# e-ink_sch.net
KiCad netlist of a schematic drawn in Altium Designer
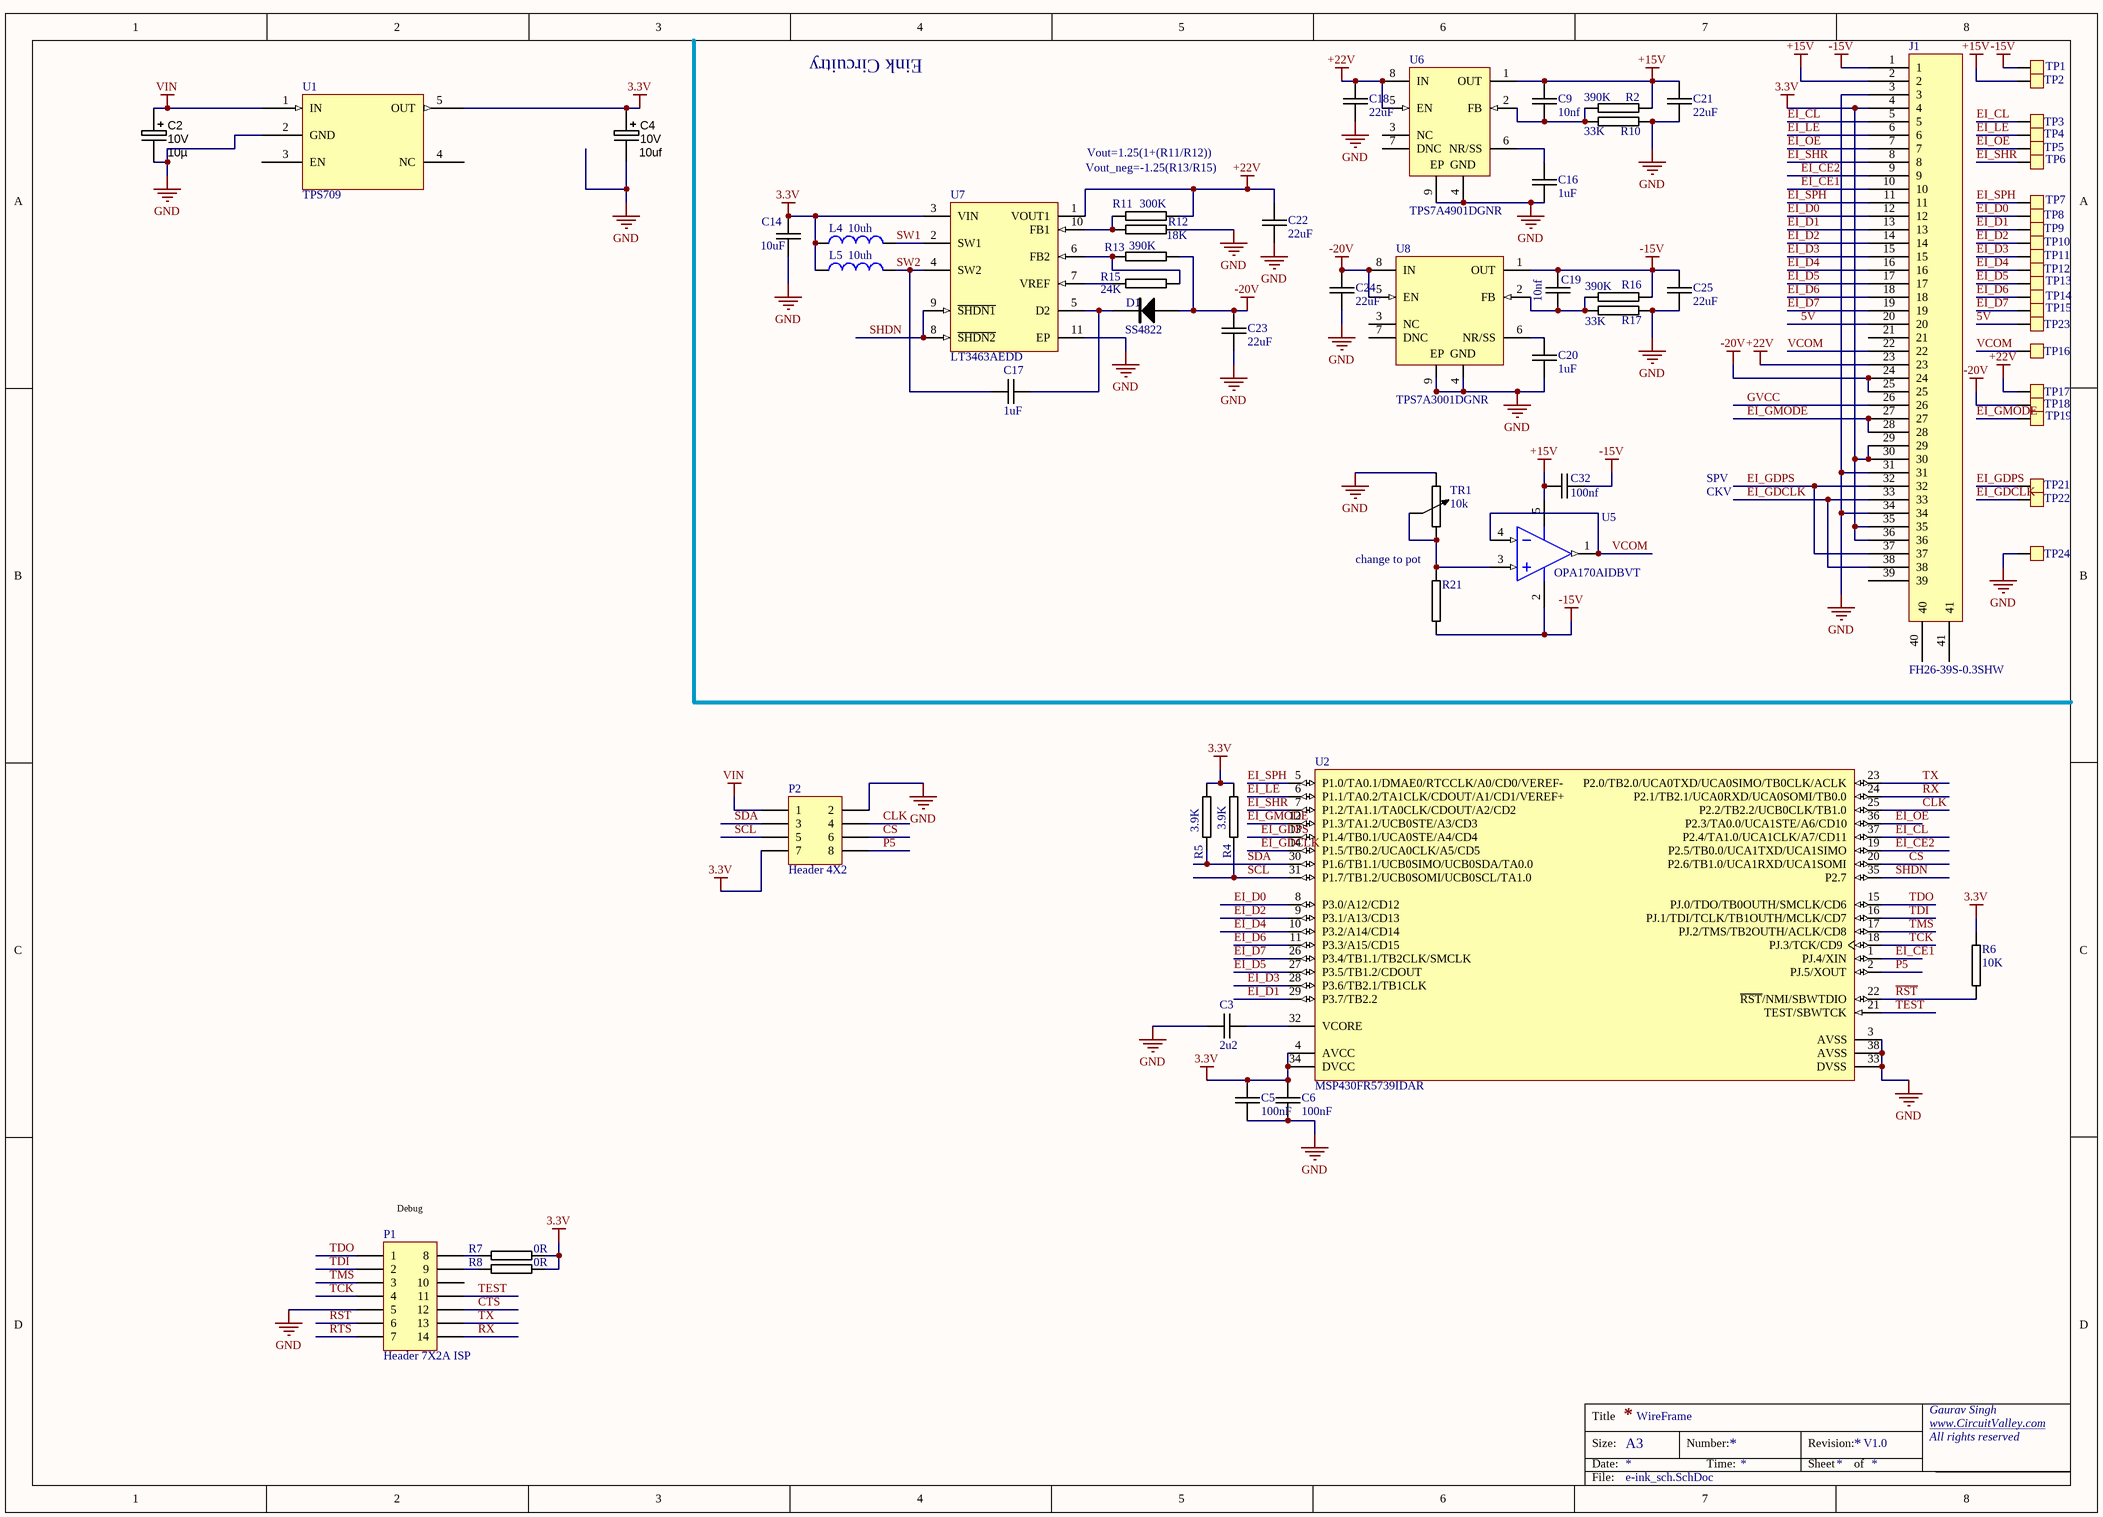
[diagram p0: e-ink_sch.SchDoc]

(export (version "E")
  (design (tool "Eeschema 10.0.6"))
  (components
    (comp (ref "C2")
      (value "10µ")
      (footprint "CAPMP3528X210N")
      (description "Capacitor SMD Tantalum 47uF 20% 6.3V 1210")
      (fields (field (name "TOLERANCE") "±20%") (field (name "RATINGS") "10V"))
      (libsource (lib "PBL - Capacitors") (part "CAPT_47u_1210_6V3"))
    )
    (comp (ref "C3")
      (value "2u2")
      (footprint "0805C-GENERIC")
      (description "CAPACITOR 0805 CERAMIC")
      (fields
        (field (name "MANUFACTURER PART NUMBER") "ECJ-1VB0J225K")
        (field (name "MANUFACTURER") "Panasonic - ECG")
      )
      (libsource (lib "Generic") (part "0805C-2U2-6V3-X5R-PAN"))
    )
    (comp (ref "C4")
      (value "10uf")
      (footprint "CAPMP3528X210N")
      (description "Capacitor SMD Tantalum 47uF 20% 6.3V 1210")
      (fields (field (name "TOLERANCE") "±20%") (field (name "RATINGS") "10V"))
      (libsource (lib "PBL - Capacitors") (part "CAPT_47u_1210_6V3"))
    )
    (comp (ref "C5")
      (value "100nF")
      (footprint "0603C-GENERIC")
      (description "CAPACITOR 0603 CERAMIC")
      (fields
        (field (name "MANUFACTURER PART NUMBER") "C1608X7R1E104K")
        (field (name "MANUFACTURER") "TDK Corporation")
      )
      (libsource (lib "Generic") (part "0603C-100NF-25V-X7R-TDK"))
    )
    (comp (ref "C6")
      (value "100nF")
      (footprint "0603C-GENERIC")
      (description "CAPACITOR 0603 CERAMIC")
      (fields
        (field (name "MANUFACTURER PART NUMBER") "C1608X7R1E104K")
        (field (name "MANUFACTURER") "TDK Corporation")
      )
      (libsource (lib "Generic") (part "0603C-100NF-25V-X7R-TDK"))
    )
    (comp (ref "C9")
      (value "10nf")
      (footprint "0603C-GENERIC")
      (description "CAPACITOR 0603 CERAMIC")
      (fields
        (field (name "MANUFACTURER") "Murata Electronics North America")
        (field (name "MANUFACTURER PART NUMBER") "GRM188R60J106ME47D")
      )
      (libsource (lib "Generic") (part "0603C-10UF-6V3-X5R-MUR"))
    )
    (comp (ref "C14")
      (value "10uF")
      (footprint "0603C-GENERIC")
      (description "CAPACITOR 0603 CERAMIC")
      (fields
        (field (name "MANUFACTURER") "Murata Electronics North America")
        (field (name "MANUFACTURER PART NUMBER") "GRM188R60J106ME47D")
      )
      (libsource (lib "Generic") (part "0603C-10UF-6V3-X5R-MUR"))
    )
    (comp (ref "C16")
      (value "1uF")
      (footprint "0603C-GENERIC")
      (description "CAPACITOR 0603 CERAMIC")
      (fields
        (field (name "MANUFACTURER") "Murata Electronics North America")
        (field (name "MANUFACTURER PART NUMBER") "GRM188R60J106ME47D")
      )
      (libsource (lib "Generic") (part "0603C-10UF-6V3-X5R-MUR"))
    )
    (comp (ref "C17")
      (value "1uF")
      (footprint "0603C-GENERIC")
      (description "CAPACITOR 0603 CERAMIC")
      (fields
        (field (name "MANUFACTURER") "Murata Electronics North America")
        (field (name "MANUFACTURER PART NUMBER") "GRM188R60J106ME47D")
      )
      (libsource (lib "Generic") (part "0603C-10UF-6V3-X5R-MUR"))
    )
    (comp (ref "C18")
      (value "22uF")
      (footprint "0603C-GENERIC")
      (description "CAPACITOR 0603 CERAMIC")
      (fields
        (field (name "MANUFACTURER") "Murata Electronics North America")
        (field (name "MANUFACTURER PART NUMBER") "GRM188R60J106ME47D")
      )
      (libsource (lib "Generic") (part "0603C-10UF-6V3-X5R-MUR"))
    )
    (comp (ref "C19")
      (value "10nf")
      (footprint "0603C-GENERIC")
      (description "CAPACITOR 0603 CERAMIC")
      (fields
        (field (name "MANUFACTURER") "Murata Electronics North America")
        (field (name "MANUFACTURER PART NUMBER") "GRM188R60J106ME47D")
      )
      (libsource (lib "Generic") (part "0603C-10UF-6V3-X5R-MUR"))
    )
    (comp (ref "C20")
      (value "1uF")
      (footprint "0603C-GENERIC")
      (description "CAPACITOR 0603 CERAMIC")
      (fields
        (field (name "MANUFACTURER") "Murata Electronics North America")
        (field (name "MANUFACTURER PART NUMBER") "GRM188R60J106ME47D")
      )
      (libsource (lib "Generic") (part "0603C-10UF-6V3-X5R-MUR"))
    )
    (comp (ref "C21")
      (value "22uF")
      (footprint "0603C-GENERIC")
      (description "CAPACITOR 0603 CERAMIC")
      (fields
        (field (name "MANUFACTURER") "Murata Electronics North America")
        (field (name "MANUFACTURER PART NUMBER") "GRM188R60J106ME47D")
      )
      (libsource (lib "Generic") (part "0603C-10UF-6V3-X5R-MUR"))
    )
    (comp (ref "C22")
      (value "22uF")
      (footprint "0603C-GENERIC")
      (description "CAPACITOR 0603 CERAMIC")
      (fields
        (field (name "MANUFACTURER") "Murata Electronics North America")
        (field (name "MANUFACTURER PART NUMBER") "GRM188R60J106ME47D")
      )
      (libsource (lib "Generic") (part "0603C-10UF-6V3-X5R-MUR"))
    )
    (comp (ref "C23")
      (value "22uF")
      (footprint "0603C-GENERIC")
      (description "CAPACITOR 0603 CERAMIC")
      (fields
        (field (name "MANUFACTURER") "Murata Electronics North America")
        (field (name "MANUFACTURER PART NUMBER") "GRM188R60J106ME47D")
      )
      (libsource (lib "Generic") (part "0603C-10UF-6V3-X5R-MUR"))
    )
    (comp (ref "C24")
      (value "22uF")
      (footprint "0603C-GENERIC")
      (description "CAPACITOR 0603 CERAMIC")
      (fields
        (field (name "MANUFACTURER") "Murata Electronics North America")
        (field (name "MANUFACTURER PART NUMBER") "GRM188R60J106ME47D")
      )
      (libsource (lib "Generic") (part "0603C-10UF-6V3-X5R-MUR"))
    )
    (comp (ref "C25")
      (value "22uF")
      (footprint "0603C-GENERIC")
      (description "CAPACITOR 0603 CERAMIC")
      (fields
        (field (name "MANUFACTURER") "Murata Electronics North America")
        (field (name "MANUFACTURER PART NUMBER") "GRM188R60J106ME47D")
      )
      (libsource (lib "Generic") (part "0603C-10UF-6V3-X5R-MUR"))
    )
    (comp (ref "C32")
      (value "100nf")
      (footprint "0603C-GENERIC")
      (description "CAPACITOR 0603 CERAMIC")
      (fields
        (field (name "MANUFACTURER") "Murata Electronics North America")
        (field (name "MANUFACTURER PART NUMBER") "GRM188R60J106ME47D")
      )
      (libsource (lib "Generic") (part "0603C-10UF-6V3-X5R-MUR"))
    )
    (comp (ref "D1")
      (value "SS4822")
      (footprint "DIODE-SMA")
      (description "DIODE")
      (libsource (lib "Generic") (part "MBRS140"))
    )
    (comp (ref "J1")
      (value "FH26-39S-0.3SHW")
      (footprint "FH26-39S-0.3SHW")
      (libsource (lib "Hiros") (part "FH26-39S-0.3SHW"))
    )
    (comp (ref "L4")
      (value "10uh")
      (footprint "IFSC-1515AH-01")
      (fields (field (name "PARTNUMBER") "IFSC1515AHER100M01"))
      (libsource (lib "Inductor") (part "inductor_smd"))
    )
    (comp (ref "L5")
      (value "10uh")
      (footprint "IFSC-1515AH-01")
      (fields (field (name "PARTNUMBER") "IFSC1515AHER100M01"))
      (libsource (lib "Inductor") (part "inductor_smd"))
    )
    (comp (ref "P1")
      (value "Header 7X2A ISP")
      (footprint "HDR2X7_CEN")
      (description "Header, 7-Pin, Dual row")
      (fields (field (name "PUBLISHER") "Altium Limited"))
      (libsource (lib "Miscellaneous Connectors") (part "Header 7X2A"))
    )
    (comp (ref "P2")
      (value "Header 4X2")
      (footprint "HDR2X4")
      (description "Header, 4-Pin, Dual row")
      (fields (field (name "PUBLISHER") "Altium Limited"))
      (libsource (lib "Miscellaneous Connectors") (part "Header 4X2"))
    )
    (comp (ref "R2")
      (value "390K")
      (footprint "0603R-2K2")
      (description "GENERIC RESISTOR 0603")
      (fields
        (field (name "MANUFACTURER PART NUMBER") "RMC 1/16 2.2K 1% R")
        (field (name "MANUFACTURER") "Stackpole Electronics Inc")
      )
      (libsource (lib "Generic") (part "0603R-2K2"))
    )
    (comp (ref "R4")
      (value "3.9K")
      (footprint "0805R-2K2")
      (description "RESISTOR 0805 1/4 WATT THIN FILM")
      (libsource (lib "Generic") (part "0805R-2K2"))
    )
    (comp (ref "R5")
      (value "3.9K")
      (footprint "0805R-2K2")
      (description "RESISTOR 0805 1/4 WATT THIN FILM")
      (libsource (lib "Generic") (part "0805R-2K2"))
    )
    (comp (ref "R6")
      (value "10K")
      (footprint "0603R-10K")
      (description "GENERIC RESISTOR 0603")
      (fields (field (name "MANUFACTURER") "Stackpole Electronics Inc") (field (name "TOLERANCE") "±1%"))
      (libsource (lib "Generic") (part "0603R-10K"))
    )
    (comp (ref "R7")
      (value "0R")
      (footprint "0805R-2K2")
      (description "RESISTOR 0805 1/4 WATT THIN FILM")
      (libsource (lib "Generic") (part "0805R-2K2"))
    )
    (comp (ref "R8")
      (value "0R")
      (footprint "0805R-2K2")
      (description "RESISTOR 0805 1/4 WATT THIN FILM")
      (libsource (lib "Generic") (part "0805R-2K2"))
    )
    (comp (ref "R10")
      (value "33K")
      (footprint "0603R-2K2")
      (description "GENERIC RESISTOR 0603")
      (fields
        (field (name "MANUFACTURER PART NUMBER") "RMC 1/16 2.2K 1% R")
        (field (name "MANUFACTURER") "Stackpole Electronics Inc")
      )
      (libsource (lib "Generic") (part "0603R-2K2"))
    )
    (comp (ref "R11")
      (value "300K")
      (footprint "0603R-2K2")
      (description "GENERIC RESISTOR 0603")
      (fields
        (field (name "MANUFACTURER PART NUMBER") "RMC 1/16 2.2K 1% R")
        (field (name "MANUFACTURER") "Stackpole Electronics Inc")
      )
      (libsource (lib "Generic") (part "0603R-2K2"))
    )
    (comp (ref "R12")
      (value "18K")
      (footprint "0603R-2K2")
      (description "GENERIC RESISTOR 0603")
      (fields
        (field (name "MANUFACTURER PART NUMBER") "RMC 1/16 2.2K 1% R")
        (field (name "MANUFACTURER") "Stackpole Electronics Inc")
      )
      (libsource (lib "Generic") (part "0603R-2K2"))
    )
    (comp (ref "R13")
      (value "390K")
      (footprint "0603R-2K2")
      (description "GENERIC RESISTOR 0603")
      (fields
        (field (name "MANUFACTURER PART NUMBER") "RMC 1/16 2.2K 1% R")
        (field (name "MANUFACTURER") "Stackpole Electronics Inc")
      )
      (libsource (lib "Generic") (part "0603R-2K2"))
    )
    (comp (ref "R15")
      (value "24K")
      (footprint "0603R-2K2")
      (description "GENERIC RESISTOR 0603")
      (fields
        (field (name "MANUFACTURER PART NUMBER") "RMC 1/16 2.2K 1% R")
        (field (name "MANUFACTURER") "Stackpole Electronics Inc")
      )
      (libsource (lib "Generic") (part "0603R-2K2"))
    )
    (comp (ref "R16")
      (value "390K")
      (footprint "0603R-2K2")
      (description "GENERIC RESISTOR 0603")
      (fields
        (field (name "MANUFACTURER PART NUMBER") "RMC 1/16 2.2K 1% R")
        (field (name "MANUFACTURER") "Stackpole Electronics Inc")
      )
      (libsource (lib "Generic") (part "0603R-2K2"))
    )
    (comp (ref "R17")
      (value "33K")
      (footprint "0603R-2K2")
      (description "GENERIC RESISTOR 0603")
      (fields
        (field (name "MANUFACTURER PART NUMBER") "RMC 1/16 2.2K 1% R")
        (field (name "MANUFACTURER") "Stackpole Electronics Inc")
      )
      (libsource (lib "Generic") (part "0603R-2K2"))
    )
    (comp (ref "R21")
      (value "unknown")
      (footprint "0603R-2K2")
      (description "GENERIC RESISTOR 0603")
      (fields
        (field (name "MANUFACTURER PART NUMBER") "RMC 1/16 2.2K 1% R")
        (field (name "MANUFACTURER") "Stackpole Electronics Inc")
      )
      (libsource (lib "Generic") (part "0603R-2K2"))
    )
    (comp (ref "TP1")
      (value "TEST_POINT")
      (footprint "SMD_TEST_3.5_2.0")
      (libsource (lib "SMD_TEST_PAD") (part "TEST_POINT"))
    )
    (comp (ref "TP2")
      (value "TEST_POINT")
      (footprint "SMD_TEST_3.5_2.0")
      (libsource (lib "SMD_TEST_PAD") (part "TEST_POINT"))
    )
    (comp (ref "TP3")
      (value "TEST_POINT")
      (footprint "SMD_TEST_3.5_2.0")
      (libsource (lib "SMD_TEST_PAD") (part "TEST_POINT"))
    )
    (comp (ref "TP4")
      (value "TEST_POINT")
      (footprint "SMD_TEST_3.5_2.0")
      (libsource (lib "SMD_TEST_PAD") (part "TEST_POINT"))
    )
    (comp (ref "TP5")
      (value "TEST_POINT")
      (footprint "SMD_TEST_3.5_2.0")
      (libsource (lib "SMD_TEST_PAD") (part "TEST_POINT"))
    )
    (comp (ref "TP6")
      (value "TEST_POINT")
      (footprint "SMD_TEST_3.5_2.0")
      (libsource (lib "SMD_TEST_PAD") (part "TEST_POINT"))
    )
    (comp (ref "TP7")
      (value "TEST_POINT")
      (footprint "SMD_TEST_3.5_2.0")
      (libsource (lib "SMD_TEST_PAD") (part "TEST_POINT"))
    )
    (comp (ref "TP8")
      (value "TEST_POINT")
      (footprint "SMD_TEST_3.5_2.0")
      (libsource (lib "SMD_TEST_PAD") (part "TEST_POINT"))
    )
    (comp (ref "TP9")
      (value "TEST_POINT")
      (footprint "SMD_TEST_3.5_2.0")
      (libsource (lib "SMD_TEST_PAD") (part "TEST_POINT"))
    )
    (comp (ref "TP10")
      (value "TEST_POINT")
      (footprint "SMD_TEST_3.5_2.0")
      (libsource (lib "SMD_TEST_PAD") (part "TEST_POINT"))
    )
    (comp (ref "TP11")
      (value "TEST_POINT")
      (footprint "SMD_TEST_3.5_2.0")
      (libsource (lib "SMD_TEST_PAD") (part "TEST_POINT"))
    )
    (comp (ref "TP12")
      (value "TEST_POINT")
      (footprint "SMD_TEST_3.5_2.0")
      (libsource (lib "SMD_TEST_PAD") (part "TEST_POINT"))
    )
    (comp (ref "TP13")
      (value "TEST_POINT")
      (footprint "SMD_TEST_3.5_2.0")
      (libsource (lib "SMD_TEST_PAD") (part "TEST_POINT"))
    )
    (comp (ref "TP14")
      (value "TEST_POINT")
      (footprint "SMD_TEST_3.5_2.0")
      (libsource (lib "SMD_TEST_PAD") (part "TEST_POINT"))
    )
    (comp (ref "TP15")
      (value "TEST_POINT")
      (footprint "SMD_TEST_3.5_2.0")
      (libsource (lib "SMD_TEST_PAD") (part "TEST_POINT"))
    )
    (comp (ref "TP16")
      (value "TEST_POINT")
      (footprint "SMD_TEST_3.5_2.0")
      (libsource (lib "SMD_TEST_PAD") (part "TEST_POINT"))
    )
    (comp (ref "TP17")
      (value "TEST_POINT")
      (footprint "SMD_TEST_3.5_2.0")
      (libsource (lib "SMD_TEST_PAD") (part "TEST_POINT"))
    )
    (comp (ref "TP18")
      (value "TEST_POINT")
      (footprint "SMD_TEST_3.5_2.0")
      (libsource (lib "SMD_TEST_PAD") (part "TEST_POINT"))
    )
    (comp (ref "TP19")
      (value "TEST_POINT")
      (footprint "SMD_TEST_3.5_2.0")
      (libsource (lib "SMD_TEST_PAD") (part "TEST_POINT"))
    )
    (comp (ref "TP21")
      (value "TEST_POINT")
      (footprint "SMD_TEST_3.5_2.0")
      (libsource (lib "SMD_TEST_PAD") (part "TEST_POINT"))
    )
    (comp (ref "TP22")
      (value "TEST_POINT")
      (footprint "SMD_TEST_3.5_2.0")
      (libsource (lib "SMD_TEST_PAD") (part "TEST_POINT"))
    )
    (comp (ref "TP23")
      (value "TEST_POINT")
      (footprint "SMD_TEST_3.5_2.0")
      (libsource (lib "SMD_TEST_PAD") (part "TEST_POINT"))
    )
    (comp (ref "TP24")
      (value "TEST_POINT")
      (footprint "SMD_TEST_3.5_2.0")
      (libsource (lib "SMD_TEST_PAD") (part "TEST_POINT"))
    )
    (comp (ref "TR1")
      (value "10k")
      (footprint "SMDPOT")
      (description "GENERIC SMD TRIMMER")
      (fields (field (name "TOLERANCE") "±10%") (field (name "MANUFACTURER PART NUMBER") "3224X-1-103E"))
      (libsource (lib "Generic") (part "R-TRIM-SMD-10k"))
    )
    (comp (ref "U1") (value "TPS709") (footprint "SOT23-5") (libsource (lib "LDO_reg") (part "TPS709")))
    (comp (ref "U2")
      (value "MSP430FR5739IDAR")
      (footprint "TI-DA38_N")
      (fields (field (name "MANUFACTURER") "Texas Instruments"))
      (libsource (lib "TI Microcontroller MSP430 16-bit Ultra-Low Power") (part "MSP430FR5739IDAR"))
    )
    (comp (ref "U5")
      (value "OPA170AIDBVT")
      (footprint "TI-DBV5_N")
      (fields (field (name "MANUFACTURER") "Texas Instruments"))
      (libsource (lib "TI Amplifiers and Linear Operational Amplifier Precision Amplifier Part One") (part "OPA244NA/250"))
    )
    (comp (ref "U6")
      (value "TPS7A4901DGNR")
      (footprint "TI-DGN8-1760X1425TP_N")
      (fields (field (name "MANUFACTURER") "Texas Instruments"))
      (libsource (lib "TI Power Management Linear Regulator Single Channel LDO (0-350mA)") (part "TPS7A4901DGNR"))
    )
    (comp (ref "U7")
      (value "LT3463AEDD")
      (footprint "LT-DD-10_V")
      (fields (field (name "MANUFACTURER") "Linear Technology"))
      (libsource (lib "Linear Technology Power Management PMIC Multifunction") (part "LT3463AEDD"))
    )
    (comp (ref "U8")
      (value "TPS7A3001DGNR")
      (footprint "TI-DGN8-1760X1425TP_N")
      (fields (field (name "MANUFACTURER") "Texas Instruments"))
      (libsource (lib "TI Power Management Linear Regulator Single Channel LDO (0-350mA)") (part "TPS7A3001DGNR"))
    )
  )
  (nets
    (net (code "1") (name "+15V") (class "Default")
      (node (ref "C21") (pin "2") (pintype "passive"))
      (node (ref "C32") (pin "2") (pintype "passive"))
      (node (ref "C9") (pin "1") (pintype "passive"))
      (node (ref "J1") (pin "2") (pinfunction "2_2") (pintype "passive"))
      (node (ref "R2") (pin "2") (pintype "passive"))
      (node (ref "TP2") (pin "0") (pinfunction "0_0") (pintype "passive"))
      (node (ref "U5") (pin "5") (pinfunction "V+_5") (pintype "power_in"))
      (node (ref "U6") (pin "1") (pinfunction "OUT_1") (pintype "power_in"))
    )
    (net (code "2") (name "+22V") (class "Default")
      (node (ref "C18") (pin "2") (pintype "passive"))
      (node (ref "C22") (pin "2") (pintype "passive"))
      (node (ref "J1") (pin "23") (pinfunction "23_23") (pintype "passive"))
      (node (ref "R11") (pin "2") (pintype "passive"))
      (node (ref "TP17") (pin "0") (pinfunction "0_0") (pintype "passive"))
      (node (ref "U6") (pin "5") (pinfunction "EN_5") (pintype "input"))
      (node (ref "U6") (pin "8") (pinfunction "IN_8") (pintype "power_in"))
      (node (ref "U7") (pin "1") (pinfunction "VOUT1_1") (pintype "power_in"))
    )
    (net (code "3") (name "-15V") (class "Default")
      (node (ref "C19") (pin "1") (pintype "passive"))
      (node (ref "C25") (pin "2") (pintype "passive"))
      (node (ref "C32") (pin "1") (pintype "passive"))
      (node (ref "J1") (pin "1") (pinfunction "1_1") (pintype "passive"))
      (node (ref "R16") (pin "2") (pintype "passive"))
      (node (ref "R21") (pin "1") (pintype "passive"))
      (node (ref "TP1") (pin "0") (pinfunction "0_0") (pintype "passive"))
      (node (ref "U5") (pin "2") (pinfunction "V-_2") (pintype "power_in"))
      (node (ref "U8") (pin "1") (pinfunction "OUT_1") (pintype "power_in"))
    )
    (net (code "4") (name "-20V") (class "Default")
      (node (ref "C23") (pin "2") (pintype "passive"))
      (node (ref "C24") (pin "2") (pintype "passive"))
      (node (ref "D1") (pin "A") (pinfunction "A_A") (pintype "passive"))
      (node (ref "J1") (pin "24") (pinfunction "24_24") (pintype "passive"))
      (node (ref "J1") (pin "25") (pinfunction "25_25") (pintype "passive"))
      (node (ref "R13") (pin "2") (pintype "passive"))
      (node (ref "TP18") (pin "0") (pinfunction "0_0") (pintype "passive"))
      (node (ref "U8") (pin "5") (pinfunction "EN_5") (pintype "input"))
      (node (ref "U8") (pin "8") (pinfunction "IN_8") (pintype "power_in"))
    )
    (net (code "5") (name "/5V") (class "Default")
      (node (ref "J1") (pin "20") (pinfunction "20_20") (pintype "passive"))
      (node (ref "TP23") (pin "0") (pinfunction "0_0") (pintype "passive"))
    )
    (net (code "6") (name "/CLK") (class "Default")
      (node (ref "P2") (pin "4") (pinfunction "4_4") (pintype "passive"))
      (node (ref "U2") (pin "25") (pinfunction "P2.2/TB2.2/UCB0CLK/TB1.0_25") (pintype "bidirectional"))
    )
    (net (code "7") (name "/CS") (class "Default")
      (node (ref "P2") (pin "6") (pinfunction "6_6") (pintype "passive"))
      (node (ref "U2") (pin "20") (pinfunction "P2.6/TB1.0/UCA1RXD/UCA1SOMI_20") (pintype "bidirectional"))
    )
    (net (code "8") (name "/CTS") (class "Default")
      (node (ref "P1") (pin "12") (pinfunction "12_12") (pintype "passive"))
    )
    (net (code "9") (name "/EI_CE1") (class "Default")
      (node (ref "J1") (pin "10") (pinfunction "10_10") (pintype "passive"))
      (node (ref "U2") (pin "1") (pinfunction "PJ.4/XIN_1") (pintype "bidirectional"))
    )
    (net (code "10") (name "/EI_CE2") (class "Default")
      (node (ref "J1") (pin "9") (pinfunction "9_9") (pintype "passive"))
      (node (ref "U2") (pin "19") (pinfunction "P2.5/TB0.0/UCA1TXD/UCA1SIMO_19") (pintype "bidirectional"))
    )
    (net (code "11") (name "/EI_CL") (class "Default")
      (node (ref "J1") (pin "5") (pinfunction "5_5") (pintype "passive"))
      (node (ref "TP3") (pin "0") (pinfunction "0_0") (pintype "passive"))
      (node (ref "U2") (pin "37") (pinfunction "P2.4/TA1.0/UCA1CLK/A7/CD11_37") (pintype "bidirectional"))
    )
    (net (code "12") (name "/EI_D0") (class "Default")
      (node (ref "J1") (pin "12") (pinfunction "12_12") (pintype "passive"))
      (node (ref "TP8") (pin "0") (pinfunction "0_0") (pintype "passive"))
      (node (ref "U2") (pin "8") (pinfunction "P3.0/A12/CD12_8") (pintype "bidirectional"))
    )
    (net (code "13") (name "/EI_D1") (class "Default")
      (node (ref "J1") (pin "13") (pinfunction "13_13") (pintype "passive"))
      (node (ref "TP9") (pin "0") (pinfunction "0_0") (pintype "passive"))
      (node (ref "U2") (pin "29") (pinfunction "P3.7/TB2.2_29") (pintype "bidirectional"))
    )
    (net (code "14") (name "/EI_D2") (class "Default")
      (node (ref "J1") (pin "14") (pinfunction "14_14") (pintype "passive"))
      (node (ref "TP10") (pin "0") (pinfunction "0_0") (pintype "passive"))
      (node (ref "U2") (pin "9") (pinfunction "P3.1/A13/CD13_9") (pintype "bidirectional"))
    )
    (net (code "15") (name "/EI_D3") (class "Default")
      (node (ref "J1") (pin "15") (pinfunction "15_15") (pintype "passive"))
      (node (ref "TP11") (pin "0") (pinfunction "0_0") (pintype "passive"))
      (node (ref "U2") (pin "28") (pinfunction "P3.6/TB2.1/TB1CLK_28") (pintype "bidirectional"))
    )
    (net (code "16") (name "/EI_D4") (class "Default")
      (node (ref "J1") (pin "16") (pinfunction "16_16") (pintype "passive"))
      (node (ref "TP12") (pin "0") (pinfunction "0_0") (pintype "passive"))
      (node (ref "U2") (pin "10") (pinfunction "P3.2/A14/CD14_10") (pintype "bidirectional"))
    )
    (net (code "17") (name "/EI_D5") (class "Default")
      (node (ref "J1") (pin "17") (pinfunction "17_17") (pintype "passive"))
      (node (ref "TP13") (pin "0") (pinfunction "0_0") (pintype "passive"))
      (node (ref "U2") (pin "27") (pinfunction "P3.5/TB1.2/CDOUT_27") (pintype "bidirectional"))
    )
    (net (code "18") (name "/EI_D6") (class "Default")
      (node (ref "J1") (pin "18") (pinfunction "18_18") (pintype "passive"))
      (node (ref "TP14") (pin "0") (pinfunction "0_0") (pintype "passive"))
      (node (ref "U2") (pin "11") (pinfunction "P3.3/A15/CD15_11") (pintype "bidirectional"))
    )
    (net (code "19") (name "/EI_D7") (class "Default")
      (node (ref "J1") (pin "19") (pinfunction "19_19") (pintype "passive"))
      (node (ref "TP15") (pin "0") (pinfunction "0_0") (pintype "passive"))
      (node (ref "U2") (pin "26") (pinfunction "P3.4/TB1.1/TB2CLK/SMCLK_26") (pintype "bidirectional"))
    )
    (net (code "20") (name "/EI_GDCLK") (class "Default")
      (node (ref "J1") (pin "33") (pinfunction "33_33") (pintype "passive"))
      (node (ref "J1") (pin "38") (pinfunction "38_38") (pintype "passive"))
      (node (ref "TP22") (pin "0") (pinfunction "0_0") (pintype "passive"))
      (node (ref "U2") (pin "14") (pinfunction "P1.5/TB0.2/UCA0CLK/A5/CD5_14") (pintype "bidirectional"))
    )
    (net (code "21") (name "/EI_GDPS") (class "Default")
      (node (ref "J1") (pin "32") (pinfunction "32_32") (pintype "passive"))
      (node (ref "J1") (pin "37") (pinfunction "37_37") (pintype "passive"))
      (node (ref "TP21") (pin "0") (pinfunction "0_0") (pintype "passive"))
      (node (ref "U2") (pin "13") (pinfunction "P1.4/TB0.1/UCA0STE/A4/CD4_13") (pintype "bidirectional"))
    )
    (net (code "22") (name "/EI_GMODE") (class "Default")
      (node (ref "J1") (pin "27") (pinfunction "27_27") (pintype "passive"))
      (node (ref "J1") (pin "28") (pinfunction "28_28") (pintype "passive"))
      (node (ref "TP19") (pin "0") (pinfunction "0_0") (pintype "passive"))
      (node (ref "U2") (pin "12") (pinfunction "P1.3/TA1.2/UCB0STE/A3/CD3_12") (pintype "bidirectional"))
    )
    (net (code "23") (name "/EI_LE") (class "Default")
      (node (ref "J1") (pin "6") (pinfunction "6_6") (pintype "passive"))
      (node (ref "TP4") (pin "0") (pinfunction "0_0") (pintype "passive"))
      (node (ref "U2") (pin "6") (pinfunction "P1.1/TA0.2/TA1CLK/CDOUT/A1/CD1/VEREF+_6") (pintype "bidirectional"))
    )
    (net (code "24") (name "/EI_OE") (class "Default")
      (node (ref "J1") (pin "7") (pinfunction "7_7") (pintype "passive"))
      (node (ref "TP5") (pin "0") (pinfunction "0_0") (pintype "passive"))
      (node (ref "U2") (pin "36") (pinfunction "P2.3/TA0.0/UCA1STE/A6/CD10_36") (pintype "bidirectional"))
    )
    (net (code "25") (name "/EI_SHR") (class "Default")
      (node (ref "J1") (pin "8") (pinfunction "8_8") (pintype "passive"))
      (node (ref "TP6") (pin "0") (pinfunction "0_0") (pintype "passive"))
      (node (ref "U2") (pin "7") (pinfunction "P1.2/TA1.1/TA0CLK/CDOUT/A2/CD2_7") (pintype "bidirectional"))
    )
    (net (code "26") (name "/EI_SPH") (class "Default")
      (node (ref "J1") (pin "11") (pinfunction "11_11") (pintype "passive"))
      (node (ref "TP7") (pin "0") (pinfunction "0_0") (pintype "passive"))
      (node (ref "U2") (pin "5") (pinfunction "P1.0/TA0.1/DMAE0/RTCCLK/A0/CD0/VEREF-_5") (pintype "bidirectional"))
    )
    (net (code "27") (name "/GVCC") (class "Default")
      (node (ref "J1") (pin "26") (pinfunction "26_26") (pintype "passive"))
    )
    (net (code "28") (name "/P5") (class "Default")
      (node (ref "P2") (pin "8") (pinfunction "8_8") (pintype "passive"))
      (node (ref "U2") (pin "2") (pinfunction "PJ.5/XOUT_2") (pintype "bidirectional"))
    )
    (net (code "29") (name "/RTS") (class "Default")
      (node (ref "P1") (pin "7") (pinfunction "7_7") (pintype "passive"))
    )
    (net (code "30") (name "/RX") (class "Default")
      (node (ref "P1") (pin "14") (pinfunction "14_14") (pintype "passive"))
      (node (ref "U2") (pin "24") (pinfunction "P2.1/TB2.1/UCA0RXD/UCA0SOMI/TB0.0_24") (pintype "bidirectional"))
    )
    (net (code "31") (name "/SCL") (class "Default")
      (node (ref "P2") (pin "5") (pinfunction "5_5") (pintype "passive"))
      (node (ref "R4") (pin "1") (pintype "passive"))
      (node (ref "U2") (pin "31") (pinfunction "P1.7/TB1.2/UCB0SOMI/UCB0SCL/TA1.0_31") (pintype "bidirectional"))
    )
    (net (code "32") (name "/SDA") (class "Default")
      (node (ref "P2") (pin "3") (pinfunction "3_3") (pintype "passive"))
      (node (ref "R5") (pin "1") (pintype "passive"))
      (node (ref "U2") (pin "30") (pinfunction "P1.6/TB1.1/UCB0SIMO/UCB0SDA/TA0.0_30") (pintype "bidirectional"))
    )
    (net (code "33") (name "/SHDN") (class "Default")
      (node (ref "U2") (pin "35") (pinfunction "P2.7_35") (pintype "bidirectional"))
      (node (ref "U7") (pin "8") (pinfunction "~{SHDN2}_8") (pintype "input"))
      (node (ref "U7") (pin "9") (pinfunction "~{SHDN1}_9") (pintype "input"))
    )
    (net (code "34") (name "/SW1") (class "Default")
      (node (ref "L4") (pin "2") (pinfunction "2_2") (pintype "passive"))
      (node (ref "U7") (pin "2") (pinfunction "SW1_2") (pintype "passive"))
    )
    (net (code "35") (name "/SW2") (class "Default")
      (node (ref "C17") (pin "2") (pintype "passive"))
      (node (ref "L5") (pin "2") (pinfunction "2_2") (pintype "passive"))
      (node (ref "U7") (pin "4") (pinfunction "SW2_4") (pintype "passive"))
    )
    (net (code "36") (name "/TCK") (class "Default")
      (node (ref "P1") (pin "4") (pinfunction "4_4") (pintype "passive"))
      (node (ref "U2") (pin "18") (pinfunction "PJ.3/TCK/CD9_18") (pintype "bidirectional"))
    )
    (net (code "37") (name "/TDI") (class "Default")
      (node (ref "P1") (pin "2") (pinfunction "2_2") (pintype "passive"))
      (node (ref "U2") (pin "16") (pinfunction "PJ.1/TDI/TCLK/TB1OUTH/MCLK/CD7_16") (pintype "bidirectional"))
    )
    (net (code "38") (name "/TDO") (class "Default")
      (node (ref "P1") (pin "1") (pinfunction "1_1") (pintype "passive"))
      (node (ref "U2") (pin "15") (pinfunction "PJ.0/TDO/TB0OUTH/SMCLK/CD6_15") (pintype "bidirectional"))
    )
    (net (code "39") (name "/TEST") (class "Default")
      (node (ref "P1") (pin "11") (pinfunction "11_11") (pintype "passive"))
      (node (ref "U2") (pin "21") (pinfunction "TEST/SBWTCK_21") (pintype "input"))
    )
    (net (code "40") (name "/TMS") (class "Default")
      (node (ref "P1") (pin "3") (pinfunction "3_3") (pintype "passive"))
      (node (ref "U2") (pin "17") (pinfunction "PJ.2/TMS/TB2OUTH/ACLK/CD8_17") (pintype "bidirectional"))
    )
    (net (code "41") (name "/TX") (class "Default")
      (node (ref "P1") (pin "13") (pinfunction "13_13") (pintype "passive"))
      (node (ref "U2") (pin "23") (pinfunction "P2.0/TB2.0/UCA0TXD/UCA0SIMO/TB0CLK/ACLK_23") (pintype "bidirectional"))
    )
    (net (code "42") (name "/VCOM") (class "Default")
      (node (ref "J1") (pin "22") (pinfunction "22_22") (pintype "passive"))
      (node (ref "TP16") (pin "0") (pinfunction "0_0") (pintype "passive"))
      (node (ref "U5") (pin "1") (pinfunction "OUT_1") (pintype "output"))
      (node (ref "U5") (pin "4") (pinfunction "IN-_4") (pintype "input"))
    )
    (net (code "43") (name "/~{RST}") (class "Default")
      (node (ref "P1") (pin "6") (pinfunction "6_6") (pintype "passive"))
      (node (ref "R6") (pin "2") (pintype "passive"))
      (node (ref "U2") (pin "22") (pinfunction "~{RST}/NMI/SBWTDIO_22") (pintype "bidirectional"))
    )
    (net (code "44") (name "3.3V") (class "Default")
      (node (ref "C14") (pin "2") (pintype "passive"))
      (node (ref "C4") (pin "1") (pintype "passive"))
      (node (ref "C5") (pin "1") (pintype "passive"))
      (node (ref "C6") (pin "1") (pintype "passive"))
      (node (ref "J1") (pin "29") (pinfunction "29_29") (pintype "passive"))
      (node (ref "J1") (pin "30") (pinfunction "30_30") (pintype "passive"))
      (node (ref "J1") (pin "35") (pinfunction "35_35") (pintype "passive"))
      (node (ref "J1") (pin "36") (pinfunction "36_36") (pintype "passive"))
      (node (ref "J1") (pin "4") (pinfunction "4_4") (pintype "passive"))
      (node (ref "L4") (pin "1") (pinfunction "1_1") (pintype "passive"))
      (node (ref "L5") (pin "1") (pinfunction "1_1") (pintype "passive"))
      (node (ref "P2") (pin "7") (pinfunction "7_7") (pintype "passive"))
      (node (ref "R4") (pin "2") (pintype "passive"))
      (node (ref "R5") (pin "2") (pintype "passive"))
      (node (ref "R6") (pin "1") (pintype "passive"))
      (node (ref "R7") (pin "1") (pintype "passive"))
      (node (ref "R8") (pin "1") (pintype "passive"))
      (node (ref "U1") (pin "5") (pinfunction "OUT_5") (pintype "output"))
      (node (ref "U2") (pin "34") (pinfunction "DVCC_34") (pintype "power_in"))
      (node (ref "U2") (pin "4") (pinfunction "AVCC_4") (pintype "power_in"))
      (node (ref "U7") (pin "3") (pinfunction "VIN_3") (pintype "power_in"))
    )
    (net (code "45") (name "GND") (class "Default")
      (node (ref "C14") (pin "1") (pintype "passive"))
      (node (ref "C16") (pin "1") (pintype "passive"))
      (node (ref "C18") (pin "1") (pintype "passive"))
      (node (ref "C2") (pin "2") (pintype "passive"))
      (node (ref "C20") (pin "2") (pintype "passive"))
      (node (ref "C21") (pin "1") (pintype "passive"))
      (node (ref "C22") (pin "1") (pintype "passive"))
      (node (ref "C23") (pin "1") (pintype "passive"))
      (node (ref "C24") (pin "1") (pintype "passive"))
      (node (ref "C25") (pin "1") (pintype "passive"))
      (node (ref "C3") (pin "1") (pintype "passive"))
      (node (ref "C4") (pin "2") (pintype "passive"))
      (node (ref "C5") (pin "2") (pintype "passive"))
      (node (ref "C6") (pin "2") (pintype "passive"))
      (node (ref "J1") (pin "3") (pinfunction "3_3") (pintype "passive"))
      (node (ref "J1") (pin "31") (pinfunction "31_31") (pintype "passive"))
      (node (ref "J1") (pin "34") (pinfunction "34_34") (pintype "passive"))
      (node (ref "P1") (pin "5") (pinfunction "5_5") (pintype "passive"))
      (node (ref "P2") (pin "2") (pinfunction "2_2") (pintype "passive"))
      (node (ref "R10") (pin "2") (pintype "passive"))
      (node (ref "R12") (pin "1") (pintype "passive"))
      (node (ref "R17") (pin "2") (pintype "passive"))
      (node (ref "TP24") (pin "0") (pinfunction "0_0") (pintype "passive"))
      (node (ref "TR1") (pin "2") (pinfunction "2_2") (pintype "passive"))
      (node (ref "U1") (pin "2") (pinfunction "GND_2") (pintype "power_in"))
      (node (ref "U2") (pin "3") (pinfunction "AVSS_3") (pintype "power_in"))
      (node (ref "U2") (pin "33") (pinfunction "DVSS_33") (pintype "power_in"))
      (node (ref "U2") (pin "38") (pinfunction "AVSS_38") (pintype "power_in"))
      (node (ref "U6") (pin "4") (pinfunction "GND_4") (pintype "power_in"))
      (node (ref "U6") (pin "9") (pinfunction "EP_9") (pintype "power_in"))
      (node (ref "U7") (pin "11") (pinfunction "EP_11") (pintype "power_in"))
      (node (ref "U8") (pin "4") (pinfunction "GND_4") (pintype "power_in"))
      (node (ref "U8") (pin "9") (pinfunction "EP_9") (pintype "passive"))
    )
    (net (code "46") (name "Net-(P1-Pad8)") (class "Default")
      (node (ref "P1") (pin "8") (pinfunction "8_8") (pintype "passive"))
      (node (ref "R7") (pin "2") (pintype "passive"))
    )
    (net (code "47") (name "Net-(P1-Pad9)") (class "Default")
      (node (ref "P1") (pin "9") (pinfunction "9_9") (pintype "passive"))
      (node (ref "R8") (pin "2") (pintype "passive"))
    )
    (net (code "48") (name "Net-(U2-VCORE)") (class "Default")
      (node (ref "C3") (pin "2") (pintype "passive"))
      (node (ref "U2") (pin "32") (pinfunction "VCORE_32") (pintype "passive"))
    )
    (net (code "49") (name "Net-(U5-IN+)") (class "Default")
      (node (ref "R21") (pin "2") (pintype "passive"))
      (node (ref "TR1") (pin "1") (pinfunction "1_1") (pintype "passive"))
      (node (ref "TR1") (pin "W") (pinfunction "W_W") (pintype "passive"))
      (node (ref "U5") (pin "3") (pinfunction "IN+_3") (pintype "input"))
    )
    (net (code "50") (name "Net-(U6-FB)") (class "Default")
      (node (ref "C9") (pin "2") (pintype "passive"))
      (node (ref "R10") (pin "1") (pintype "passive"))
      (node (ref "R2") (pin "1") (pintype "passive"))
      (node (ref "U6") (pin "2") (pinfunction "FB_2") (pintype "input"))
    )
    (net (code "51") (name "Net-(U6-NR{slash}SS)") (class "Default")
      (node (ref "C16") (pin "2") (pintype "passive"))
      (node (ref "U6") (pin "6") (pinfunction "NR/SS_6") (pintype "passive"))
    )
    (net (code "52") (name "Net-(U7-D2)") (class "Default")
      (node (ref "C17") (pin "1") (pintype "passive"))
      (node (ref "D1") (pin "K") (pinfunction "K_K") (pintype "passive"))
      (node (ref "U7") (pin "5") (pinfunction "D2_5") (pintype "passive"))
    )
    (net (code "53") (name "Net-(U7-FB1)") (class "Default")
      (node (ref "R11") (pin "1") (pintype "passive"))
      (node (ref "R12") (pin "2") (pintype "passive"))
      (node (ref "U7") (pin "10") (pinfunction "FB1_10") (pintype "input"))
    )
    (net (code "54") (name "Net-(U7-FB2)") (class "Default")
      (node (ref "R13") (pin "1") (pintype "passive"))
      (node (ref "R15") (pin "2") (pintype "passive"))
      (node (ref "U7") (pin "6") (pinfunction "FB2_6") (pintype "input"))
    )
    (net (code "55") (name "Net-(U7-VREF)") (class "Default")
      (node (ref "R15") (pin "1") (pintype "passive"))
      (node (ref "U7") (pin "7") (pinfunction "VREF_7") (pintype "input"))
    )
    (net (code "56") (name "Net-(U8-FB)") (class "Default")
      (node (ref "C19") (pin "2") (pintype "passive"))
      (node (ref "R16") (pin "1") (pintype "passive"))
      (node (ref "R17") (pin "1") (pintype "passive"))
      (node (ref "U8") (pin "2") (pinfunction "FB_2") (pintype "input"))
    )
    (net (code "57") (name "Net-(U8-NR{slash}SS)") (class "Default")
      (node (ref "C20") (pin "1") (pintype "passive"))
      (node (ref "U8") (pin "6") (pinfunction "NR/SS_6") (pintype "passive"))
    )
    (net (code "58") (name "VIN") (class "Default")
      (node (ref "C2") (pin "1") (pintype "passive"))
      (node (ref "P2") (pin "1") (pinfunction "1_1") (pintype "passive"))
      (node (ref "U1") (pin "1") (pinfunction "IN_1") (pintype "input"))
    )
    (net (code "59") (name "unconnected-(J1-Pad21)") (class "Default")
      (node (ref "J1") (pin "21") (pinfunction "21_21") (pintype "passive"))
    )
    (net (code "60") (name "unconnected-(J1-Pad39)") (class "Default")
      (node (ref "J1") (pin "39") (pinfunction "39_39") (pintype "passive"))
    )
    (net (code "61") (name "unconnected-(J1-Pad40)") (class "Default")
      (node (ref "J1") (pin "40") (pinfunction "40_40") (pintype "passive"))
    )
    (net (code "62") (name "unconnected-(J1-Pad41)") (class "Default")
      (node (ref "J1") (pin "41") (pinfunction "41_41") (pintype "passive"))
    )
    (net (code "63") (name "unconnected-(P1-Pad10)") (class "Default")
      (node (ref "P1") (pin "10") (pinfunction "10_10") (pintype "passive"))
    )
    (net (code "64") (name "unconnected-(U1-EN-Pad3)") (class "Default")
      (node (ref "U1") (pin "3") (pinfunction "EN_3") (pintype "passive"))
    )
    (net (code "65") (name "unconnected-(U1-NC-Pad4)") (class "Default")
      (node (ref "U1") (pin "4") (pinfunction "NC_4") (pintype "passive"))
    )
    (net (code "66") (name "unconnected-(U6-DNC-Pad7)") (class "Default")
      (node (ref "U6") (pin "7") (pinfunction "DNC_7") (pintype "passive"))
    )
    (net (code "67") (name "unconnected-(U6-NC-Pad3)") (class "Default")
      (node (ref "U6") (pin "3") (pinfunction "NC_3") (pintype "passive"))
    )
    (net (code "68") (name "unconnected-(U8-DNC-Pad7)") (class "Default")
      (node (ref "U8") (pin "7") (pinfunction "DNC_7") (pintype "passive"))
    )
    (net (code "69") (name "unconnected-(U8-NC-Pad3)") (class "Default")
      (node (ref "U8") (pin "3") (pinfunction "NC_3") (pintype "passive"))
    )
  )
)
